# driver.net
KiCad netlist of a schematic drawn in EAGLE
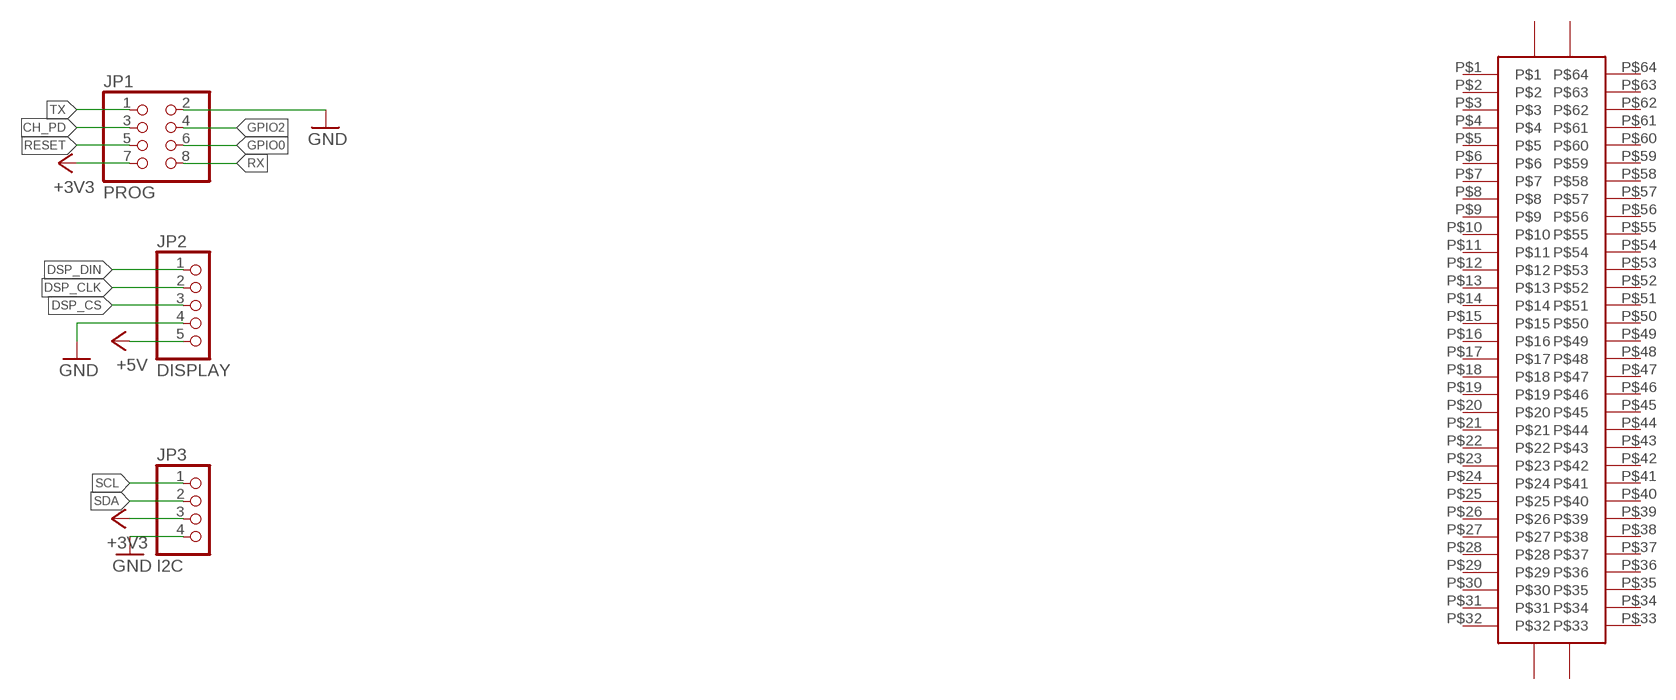
[diagram p0: schematic, sheet 1]

(export (version "E")
  (design (tool "Eeschema 10.0.6"))
  (components
    (comp (ref "JP1")
      (value "PROG")
      (footprint "eagle-import:2X04")
      (libsource (lib "eagle-import") (part "PINHD-2X4"))
    )
    (comp (ref "JP2")
      (value "DISPLAY")
      (footprint "eagle-import:1X05")
      (libsource (lib "eagle-import") (part "PINHD-1X5"))
    )
    (comp (ref "JP3")
      (value "I2C")
      (footprint "eagle-import:1X04")
      (libsource (lib "eagle-import") (part "PINHD-1X4"))
    )
    (comp (ref "U$1")
      (value "ANGLE_BOARD_CONNECTORTWO_SIDED")
      (footprint "eagle-import:TWO_SIDED")
      (libsource (lib "eagle-import") (part "ANGLE_BOARD_CONNECTORTWO_SIDED"))
    )
  )
  (nets
    (net (code "1") (name "+3V3") (class "Default")
      (node (ref "JP1") (pin "7") (pinfunction "7_7") (pintype "passive"))
      (node (ref "JP3") (pin "3") (pinfunction "3_3") (pintype "passive"))
    )
    (net (code "2") (name "+5V") (class "Default")
      (node (ref "JP2") (pin "5") (pinfunction "5_5") (pintype "passive"))
    )
    (net (code "3") (name "CH_PD") (class "Default")
      (node (ref "JP1") (pin "3") (pinfunction "3_3") (pintype "passive"))
    )
    (net (code "4") (name "DSP_CLK") (class "Default")
      (node (ref "JP2") (pin "2") (pinfunction "2_2") (pintype "passive"))
    )
    (net (code "5") (name "DSP_CS") (class "Default")
      (node (ref "JP2") (pin "3") (pinfunction "3_3") (pintype "passive"))
    )
    (net (code "6") (name "DSP_DIN") (class "Default")
      (node (ref "JP2") (pin "1") (pinfunction "1_1") (pintype "passive"))
    )
    (net (code "7") (name "GND") (class "Default")
      (node (ref "JP1") (pin "2") (pinfunction "2_2") (pintype "passive"))
      (node (ref "JP2") (pin "4") (pinfunction "4_4") (pintype "passive"))
      (node (ref "JP3") (pin "4") (pinfunction "4_4") (pintype "passive"))
    )
    (net (code "8") (name "GPIO0") (class "Default")
      (node (ref "JP1") (pin "6") (pinfunction "6_6") (pintype "passive"))
    )
    (net (code "9") (name "GPIO2") (class "Default")
      (node (ref "JP1") (pin "4") (pinfunction "4_4") (pintype "passive"))
    )
    (net (code "10") (name "RESET") (class "Default")
      (node (ref "JP1") (pin "5") (pinfunction "5_5") (pintype "passive"))
    )
    (net (code "11") (name "RX") (class "Default")
      (node (ref "JP1") (pin "8") (pinfunction "8_8") (pintype "passive"))
    )
    (net (code "12") (name "SCL") (class "Default")
      (node (ref "JP3") (pin "1") (pinfunction "1_1") (pintype "passive"))
    )
    (net (code "13") (name "SDA") (class "Default")
      (node (ref "JP3") (pin "2") (pinfunction "2_2") (pintype "passive"))
    )
    (net (code "14") (name "TX") (class "Default")
      (node (ref "JP1") (pin "1") (pinfunction "1_1") (pintype "passive"))
    )
    (net (code "15") (name "unconnected-(U$1-GND-PadGND@1)") (class "Default")
      (node (ref "U$1") (pin "GND@1") (pinfunction "GND_GND@1") (pintype "bidirectional"))
    )
    (net (code "16") (name "unconnected-(U$1-GND-PadGND@2)") (class "Default")
      (node (ref "U$1") (pin "GND@2") (pinfunction "GND_GND@2") (pintype "bidirectional"))
    )
    (net (code "17") (name "unconnected-(U$1-GND-PadGND@3)") (class "Default")
      (node (ref "U$1") (pin "GND@3") (pinfunction "GND_GND@3") (pintype "bidirectional"))
    )
    (net (code "18") (name "unconnected-(U$1-GND-PadGND@4)") (class "Default")
      (node (ref "U$1") (pin "GND@4") (pinfunction "GND_GND@4") (pintype "bidirectional"))
    )
    (net (code "19") (name "unconnected-(U$1-PadP$1)") (class "Default")
      (node (ref "U$1") (pin "P$1") (pinfunction "P$1_P$1") (pintype "bidirectional"))
    )
    (net (code "20") (name "unconnected-(U$1-PadP$2)") (class "Default")
      (node (ref "U$1") (pin "P$2") (pinfunction "P$2_P$2") (pintype "bidirectional"))
    )
    (net (code "21") (name "unconnected-(U$1-PadP$3)") (class "Default")
      (node (ref "U$1") (pin "P$3") (pinfunction "P$3_P$3") (pintype "bidirectional"))
    )
    (net (code "22") (name "unconnected-(U$1-PadP$4)") (class "Default")
      (node (ref "U$1") (pin "P$4") (pinfunction "P$4_P$4") (pintype "bidirectional"))
    )
    (net (code "23") (name "unconnected-(U$1-PadP$5)") (class "Default")
      (node (ref "U$1") (pin "P$5") (pinfunction "P$5_P$5") (pintype "bidirectional"))
    )
    (net (code "24") (name "unconnected-(U$1-PadP$6)") (class "Default")
      (node (ref "U$1") (pin "P$6") (pinfunction "P$6_P$6") (pintype "bidirectional"))
    )
    (net (code "25") (name "unconnected-(U$1-PadP$7)") (class "Default")
      (node (ref "U$1") (pin "P$7") (pinfunction "P$7_P$7") (pintype "bidirectional"))
    )
    (net (code "26") (name "unconnected-(U$1-PadP$8)") (class "Default")
      (node (ref "U$1") (pin "P$8") (pinfunction "P$8_P$8") (pintype "bidirectional"))
    )
    (net (code "27") (name "unconnected-(U$1-PadP$9)") (class "Default")
      (node (ref "U$1") (pin "P$9") (pinfunction "P$9_P$9") (pintype "bidirectional"))
    )
    (net (code "28") (name "unconnected-(U$1-PadP$10)") (class "Default")
      (node (ref "U$1") (pin "P$10") (pinfunction "P$10_P$10") (pintype "bidirectional"))
    )
    (net (code "29") (name "unconnected-(U$1-PadP$11)") (class "Default")
      (node (ref "U$1") (pin "P$11") (pinfunction "P$11_P$11") (pintype "bidirectional"))
    )
    (net (code "30") (name "unconnected-(U$1-PadP$12)") (class "Default")
      (node (ref "U$1") (pin "P$12") (pinfunction "P$12_P$12") (pintype "bidirectional"))
    )
    (net (code "31") (name "unconnected-(U$1-PadP$13)") (class "Default")
      (node (ref "U$1") (pin "P$13") (pinfunction "P$13_P$13") (pintype "bidirectional"))
    )
    (net (code "32") (name "unconnected-(U$1-PadP$14)") (class "Default")
      (node (ref "U$1") (pin "P$14") (pinfunction "P$14_P$14") (pintype "bidirectional"))
    )
    (net (code "33") (name "unconnected-(U$1-PadP$15)") (class "Default")
      (node (ref "U$1") (pin "P$15") (pinfunction "P$15_P$15") (pintype "bidirectional"))
    )
    (net (code "34") (name "unconnected-(U$1-PadP$16)") (class "Default")
      (node (ref "U$1") (pin "P$16") (pinfunction "P$16_P$16") (pintype "bidirectional"))
    )
    (net (code "35") (name "unconnected-(U$1-PadP$17)") (class "Default")
      (node (ref "U$1") (pin "P$17") (pinfunction "P$17_P$17") (pintype "bidirectional"))
    )
    (net (code "36") (name "unconnected-(U$1-PadP$18)") (class "Default")
      (node (ref "U$1") (pin "P$18") (pinfunction "P$18_P$18") (pintype "bidirectional"))
    )
    (net (code "37") (name "unconnected-(U$1-PadP$19)") (class "Default")
      (node (ref "U$1") (pin "P$19") (pinfunction "P$19_P$19") (pintype "bidirectional"))
    )
    (net (code "38") (name "unconnected-(U$1-PadP$20)") (class "Default")
      (node (ref "U$1") (pin "P$20") (pinfunction "P$20_P$20") (pintype "bidirectional"))
    )
    (net (code "39") (name "unconnected-(U$1-PadP$21)") (class "Default")
      (node (ref "U$1") (pin "P$21") (pinfunction "P$21_P$21") (pintype "bidirectional"))
    )
    (net (code "40") (name "unconnected-(U$1-PadP$22)") (class "Default")
      (node (ref "U$1") (pin "P$22") (pinfunction "P$22_P$22") (pintype "bidirectional"))
    )
    (net (code "41") (name "unconnected-(U$1-PadP$23)") (class "Default")
      (node (ref "U$1") (pin "P$23") (pinfunction "P$23_P$23") (pintype "bidirectional"))
    )
    (net (code "42") (name "unconnected-(U$1-PadP$24)") (class "Default")
      (node (ref "U$1") (pin "P$24") (pinfunction "P$24_P$24") (pintype "bidirectional"))
    )
    (net (code "43") (name "unconnected-(U$1-PadP$25)") (class "Default")
      (node (ref "U$1") (pin "P$25") (pinfunction "P$25_P$25") (pintype "bidirectional"))
    )
    (net (code "44") (name "unconnected-(U$1-PadP$26)") (class "Default")
      (node (ref "U$1") (pin "P$26") (pinfunction "P$26_P$26") (pintype "bidirectional"))
    )
    (net (code "45") (name "unconnected-(U$1-PadP$27)") (class "Default")
      (node (ref "U$1") (pin "P$27") (pinfunction "P$27_P$27") (pintype "bidirectional"))
    )
    (net (code "46") (name "unconnected-(U$1-PadP$28)") (class "Default")
      (node (ref "U$1") (pin "P$28") (pinfunction "P$28_P$28") (pintype "bidirectional"))
    )
    (net (code "47") (name "unconnected-(U$1-PadP$29)") (class "Default")
      (node (ref "U$1") (pin "P$29") (pinfunction "P$29_P$29") (pintype "bidirectional"))
    )
    (net (code "48") (name "unconnected-(U$1-PadP$30)") (class "Default")
      (node (ref "U$1") (pin "P$30") (pinfunction "P$30_P$30") (pintype "bidirectional"))
    )
    (net (code "49") (name "unconnected-(U$1-PadP$31)") (class "Default")
      (node (ref "U$1") (pin "P$31") (pinfunction "P$31_P$31") (pintype "bidirectional"))
    )
    (net (code "50") (name "unconnected-(U$1-PadP$32)") (class "Default")
      (node (ref "U$1") (pin "P$32") (pinfunction "P$32_P$32") (pintype "bidirectional"))
    )
    (net (code "51") (name "unconnected-(U$1-PadP$33)") (class "Default")
      (node (ref "U$1") (pin "P$33") (pinfunction "P$33_P$33") (pintype "bidirectional"))
    )
    (net (code "52") (name "unconnected-(U$1-PadP$34)") (class "Default")
      (node (ref "U$1") (pin "P$34") (pinfunction "P$34_P$34") (pintype "bidirectional"))
    )
    (net (code "53") (name "unconnected-(U$1-PadP$35)") (class "Default")
      (node (ref "U$1") (pin "P$35") (pinfunction "P$35_P$35") (pintype "bidirectional"))
    )
    (net (code "54") (name "unconnected-(U$1-PadP$36)") (class "Default")
      (node (ref "U$1") (pin "P$36") (pinfunction "P$36_P$36") (pintype "bidirectional"))
    )
    (net (code "55") (name "unconnected-(U$1-PadP$37)") (class "Default")
      (node (ref "U$1") (pin "P$37") (pinfunction "P$37_P$37") (pintype "bidirectional"))
    )
    (net (code "56") (name "unconnected-(U$1-PadP$38)") (class "Default")
      (node (ref "U$1") (pin "P$38") (pinfunction "P$38_P$38") (pintype "bidirectional"))
    )
    (net (code "57") (name "unconnected-(U$1-PadP$39)") (class "Default")
      (node (ref "U$1") (pin "P$39") (pinfunction "P$39_P$39") (pintype "bidirectional"))
    )
    (net (code "58") (name "unconnected-(U$1-PadP$40)") (class "Default")
      (node (ref "U$1") (pin "P$40") (pinfunction "P$40_P$40") (pintype "bidirectional"))
    )
    (net (code "59") (name "unconnected-(U$1-PadP$41)") (class "Default")
      (node (ref "U$1") (pin "P$41") (pinfunction "P$41_P$41") (pintype "bidirectional"))
    )
    (net (code "60") (name "unconnected-(U$1-PadP$42)") (class "Default")
      (node (ref "U$1") (pin "P$42") (pinfunction "P$42_P$42") (pintype "bidirectional"))
    )
    (net (code "61") (name "unconnected-(U$1-PadP$43)") (class "Default")
      (node (ref "U$1") (pin "P$43") (pinfunction "P$43_P$43") (pintype "bidirectional"))
    )
    (net (code "62") (name "unconnected-(U$1-PadP$44)") (class "Default")
      (node (ref "U$1") (pin "P$44") (pinfunction "P$44_P$44") (pintype "bidirectional"))
    )
    (net (code "63") (name "unconnected-(U$1-PadP$45)") (class "Default")
      (node (ref "U$1") (pin "P$45") (pinfunction "P$45_P$45") (pintype "bidirectional"))
    )
    (net (code "64") (name "unconnected-(U$1-PadP$46)") (class "Default")
      (node (ref "U$1") (pin "P$46") (pinfunction "P$46_P$46") (pintype "bidirectional"))
    )
    (net (code "65") (name "unconnected-(U$1-PadP$47)") (class "Default")
      (node (ref "U$1") (pin "P$47") (pinfunction "P$47_P$47") (pintype "bidirectional"))
    )
    (net (code "66") (name "unconnected-(U$1-PadP$48)") (class "Default")
      (node (ref "U$1") (pin "P$48") (pinfunction "P$48_P$48") (pintype "bidirectional"))
    )
    (net (code "67") (name "unconnected-(U$1-PadP$49)") (class "Default")
      (node (ref "U$1") (pin "P$49") (pinfunction "P$49_P$49") (pintype "bidirectional"))
    )
    (net (code "68") (name "unconnected-(U$1-PadP$50)") (class "Default")
      (node (ref "U$1") (pin "P$50") (pinfunction "P$50_P$50") (pintype "bidirectional"))
    )
    (net (code "69") (name "unconnected-(U$1-PadP$51)") (class "Default")
      (node (ref "U$1") (pin "P$51") (pinfunction "P$51_P$51") (pintype "bidirectional"))
    )
    (net (code "70") (name "unconnected-(U$1-PadP$52)") (class "Default")
      (node (ref "U$1") (pin "P$52") (pinfunction "P$52_P$52") (pintype "bidirectional"))
    )
    (net (code "71") (name "unconnected-(U$1-PadP$53)") (class "Default")
      (node (ref "U$1") (pin "P$53") (pinfunction "P$53_P$53") (pintype "bidirectional"))
    )
    (net (code "72") (name "unconnected-(U$1-PadP$54)") (class "Default")
      (node (ref "U$1") (pin "P$54") (pinfunction "P$54_P$54") (pintype "bidirectional"))
    )
    (net (code "73") (name "unconnected-(U$1-PadP$55)") (class "Default")
      (node (ref "U$1") (pin "P$55") (pinfunction "P$55_P$55") (pintype "bidirectional"))
    )
    (net (code "74") (name "unconnected-(U$1-PadP$56)") (class "Default")
      (node (ref "U$1") (pin "P$56") (pinfunction "P$56_P$56") (pintype "bidirectional"))
    )
    (net (code "75") (name "unconnected-(U$1-PadP$57)") (class "Default")
      (node (ref "U$1") (pin "P$57") (pinfunction "P$57_P$57") (pintype "bidirectional"))
    )
    (net (code "76") (name "unconnected-(U$1-PadP$58)") (class "Default")
      (node (ref "U$1") (pin "P$58") (pinfunction "P$58_P$58") (pintype "bidirectional"))
    )
    (net (code "77") (name "unconnected-(U$1-PadP$59)") (class "Default")
      (node (ref "U$1") (pin "P$59") (pinfunction "P$59_P$59") (pintype "bidirectional"))
    )
    (net (code "78") (name "unconnected-(U$1-PadP$60)") (class "Default")
      (node (ref "U$1") (pin "P$60") (pinfunction "P$60_P$60") (pintype "bidirectional"))
    )
    (net (code "79") (name "unconnected-(U$1-PadP$61)") (class "Default")
      (node (ref "U$1") (pin "P$61") (pinfunction "P$61_P$61") (pintype "bidirectional"))
    )
    (net (code "80") (name "unconnected-(U$1-PadP$62)") (class "Default")
      (node (ref "U$1") (pin "P$62") (pinfunction "P$62_P$62") (pintype "bidirectional"))
    )
    (net (code "81") (name "unconnected-(U$1-PadP$63)") (class "Default")
      (node (ref "U$1") (pin "P$63") (pinfunction "P$63_P$63") (pintype "bidirectional"))
    )
    (net (code "82") (name "unconnected-(U$1-PadP$64)") (class "Default")
      (node (ref "U$1") (pin "P$64") (pinfunction "P$64_P$64") (pintype "bidirectional"))
    )
  )
)
